# Controler_2_25.net
KiCad netlist of a schematic drawn in EAGLE
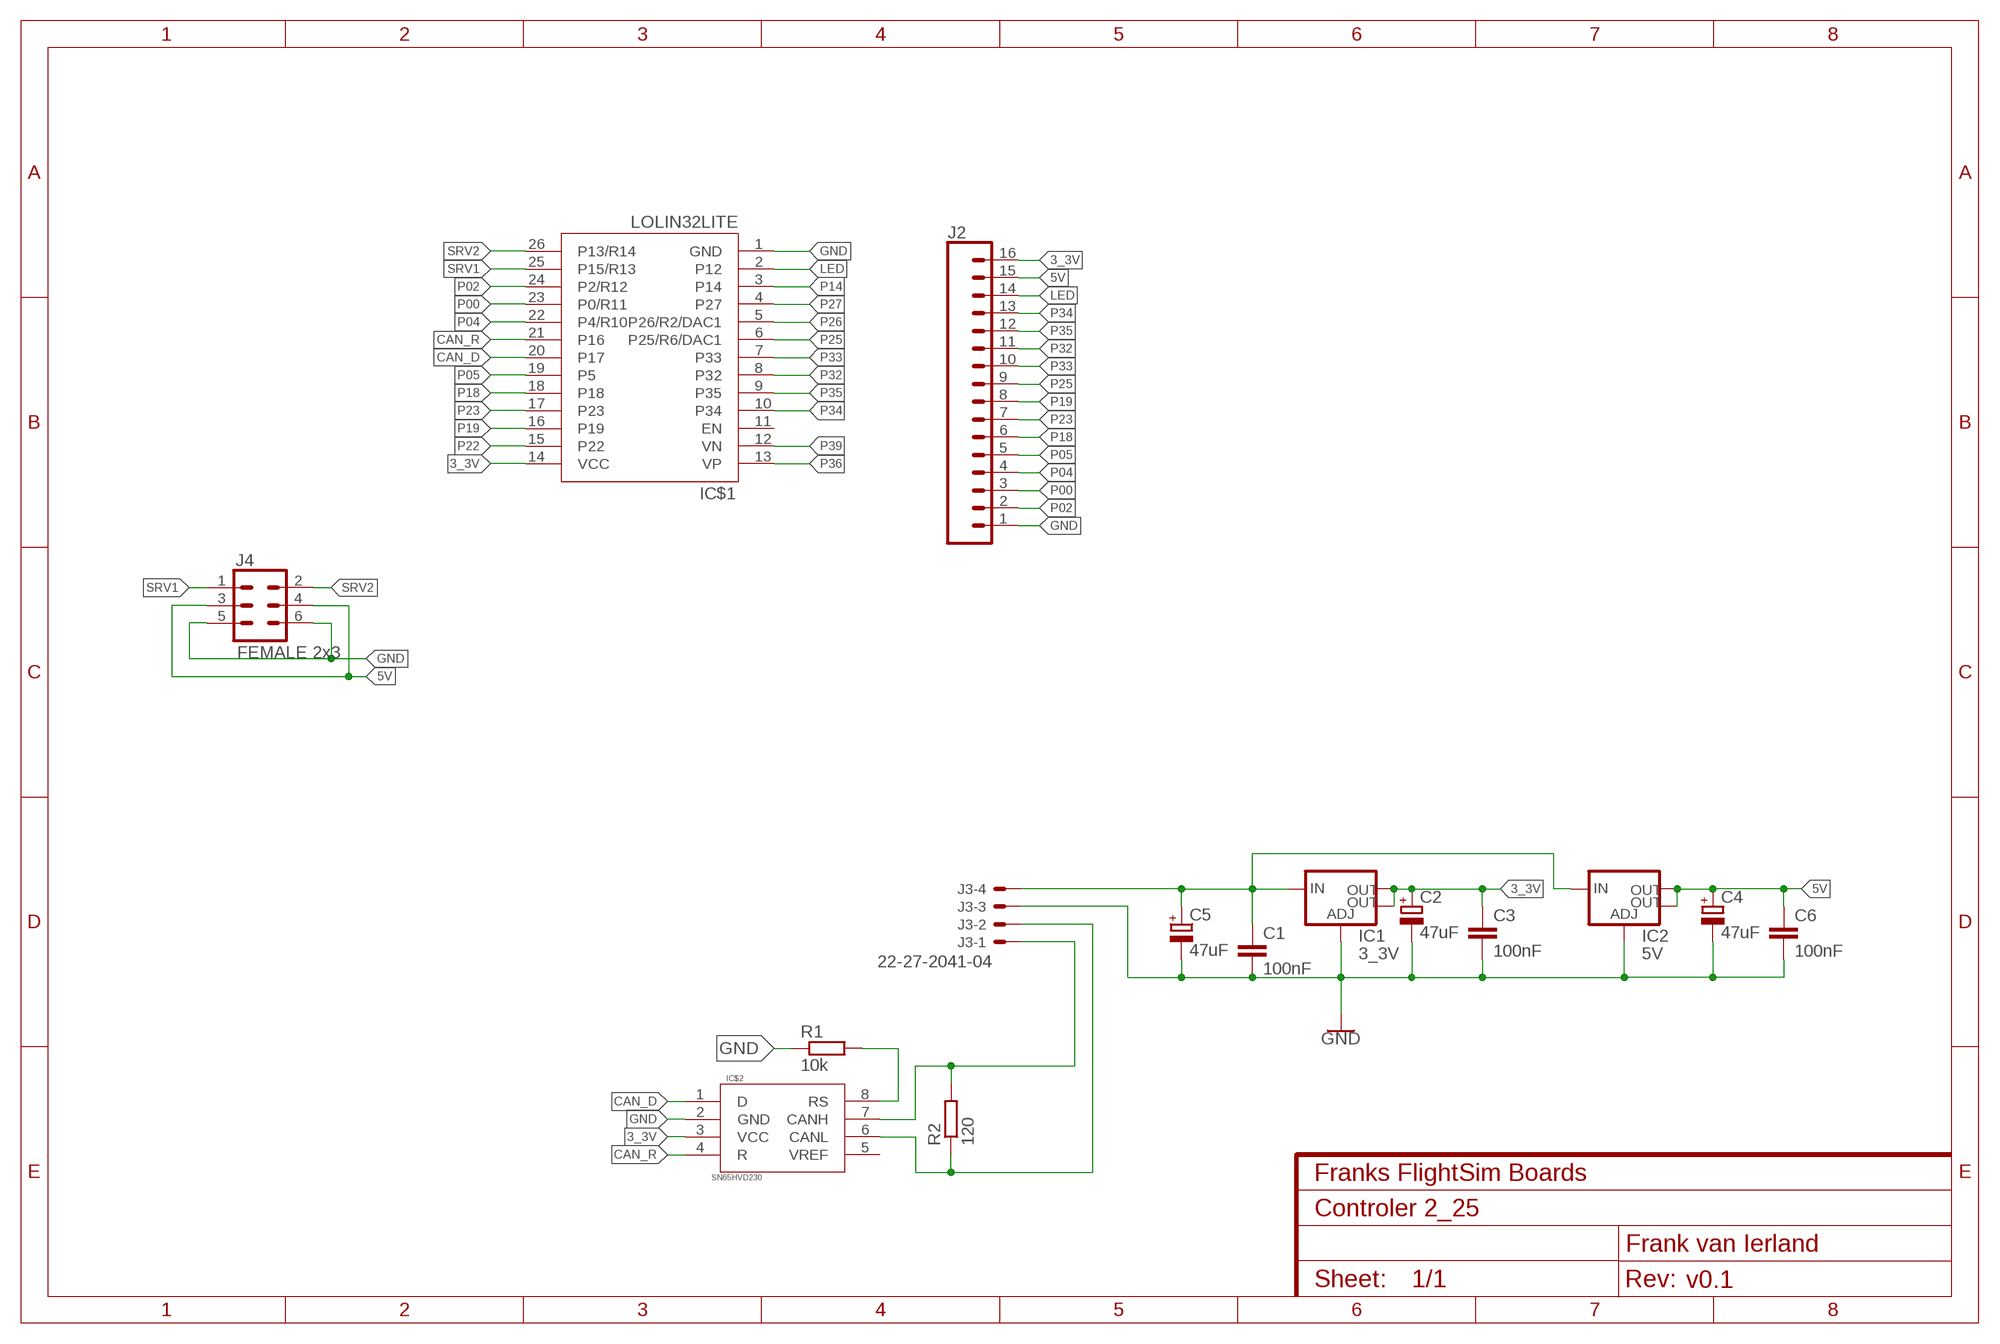
[diagram p0: schematic, sheet 1]

(export (version "E")
  (design (tool "Eeschema 10.0.6"))
  (components
    (comp (ref "C1")
      (value "100nF")
      (footprint "eagle-import:C1206")
      (libsource (lib "eagle-import") (part "C-EUC1206"))
    )
    (comp (ref "C2")
      (value "47uF")
      (footprint "eagle-import:CT3528")
      (libsource (lib "eagle-import") (part "CPOL-EUCT3528"))
    )
    (comp (ref "C3")
      (value "100nF")
      (footprint "eagle-import:C1206")
      (libsource (lib "eagle-import") (part "C-EUC1206"))
    )
    (comp (ref "C4")
      (value "47uF")
      (footprint "eagle-import:CT3528")
      (libsource (lib "eagle-import") (part "CPOL-EUCT3528"))
    )
    (comp (ref "C5")
      (value "47uF")
      (footprint "eagle-import:153CLV-0605")
      (libsource (lib "eagle-import") (part "CPOL-EU153CLV-0605"))
    )
    (comp (ref "C6")
      (value "100nF")
      (footprint "eagle-import:C1206")
      (libsource (lib "eagle-import") (part "C-EUC1206"))
    )
    (comp (ref "IC$1")
      (value "LOLIN32LITE")
      (footprint "eagle-import:LOLIN32LITE")
      (libsource (lib "eagle-import") (part "LOLIN32LITE"))
    )
    (comp (ref "IC$2")
      (value "SN65HVD230")
      (footprint "eagle-import:SO08")
      (libsource (lib "eagle-import") (part "SN65HVD230"))
    )
    (comp (ref "IC1")
      (value "3_3V")
      (footprint "eagle-import:SOT223")
      (libsource (lib "eagle-import") (part "V_REG_LM1117SOT223"))
    )
    (comp (ref "IC2")
      (value "5V")
      (footprint "eagle-import:SOT223")
      (libsource (lib "eagle-import") (part "V_REG_LM1117SOT223"))
    )
    (comp (ref "J2")
      (value "CONN_16")
      (footprint "eagle-import:1X16")
      (libsource (lib "eagle-import") (part "CONN_16"))
    )
    (comp (ref "J3")
      (value "22-27-2041-04")
      (footprint "eagle-import:6410-04")
      (fields (field (name "MF") "MOLEX"))
      (libsource (lib "eagle-import") (part "22-?-0427-2041"))
    )
    (comp (ref "J4")
      (value "FEMALE 2x3")
      (footprint "eagle-import:2X3")
      (libsource (lib "eagle-import") (part "CONN_03X2FEMALE"))
    )
    (comp (ref "R1")
      (value "10k")
      (footprint "eagle-import:M1206")
      (libsource (lib "eagle-import") (part "R-EU_M1206"))
    )
    (comp (ref "R2")
      (value "120")
      (footprint "eagle-import:R1210")
      (libsource (lib "eagle-import") (part "R-EU_R1210"))
    )
  )
  (nets
    (net (code "1") (name "3_3V") (class "Default")
      (node (ref "C2") (pin "-") (pinfunction "+_-") (pintype "passive"))
      (node (ref "C3") (pin "1") (pinfunction "1_1") (pintype "passive"))
      (node (ref "IC$1") (pin "14") (pinfunction "VCC_14") (pintype "power_in"))
      (node (ref "IC$2") (pin "3") (pinfunction "VCC_3") (pintype "bidirectional"))
      (node (ref "IC1") (pin "2") (pinfunction "OUT_2") (pintype "output"))
      (node (ref "IC1") (pin "4") (pinfunction "OUT_4") (pintype "output"))
      (node (ref "J2") (pin "16") (pinfunction "16_16") (pintype "passive"))
    )
    (net (code "2") (name "5V") (class "Default")
      (node (ref "C4") (pin "-") (pinfunction "+_-") (pintype "passive"))
      (node (ref "C6") (pin "1") (pinfunction "1_1") (pintype "passive"))
      (node (ref "IC2") (pin "2") (pinfunction "OUT_2") (pintype "output"))
      (node (ref "IC2") (pin "4") (pinfunction "OUT_4") (pintype "output"))
      (node (ref "J2") (pin "15") (pinfunction "15_15") (pintype "passive"))
      (node (ref "J4") (pin "3") (pinfunction "3_3") (pintype "bidirectional"))
      (node (ref "J4") (pin "4") (pinfunction "4_4") (pintype "bidirectional"))
    )
    (net (code "3") (name "CAN_D") (class "Default")
      (node (ref "IC$1") (pin "20") (pinfunction "P17_20") (pintype "bidirectional"))
      (node (ref "IC$2") (pin "1") (pinfunction "D_1") (pintype "bidirectional"))
    )
    (net (code "4") (name "CAN_R") (class "Default")
      (node (ref "IC$1") (pin "21") (pinfunction "P16_21") (pintype "bidirectional"))
      (node (ref "IC$2") (pin "4") (pinfunction "R_4") (pintype "bidirectional"))
    )
    (net (code "5") (name "GND") (class "Default")
      (node (ref "C1") (pin "2") (pinfunction "2_2") (pintype "passive"))
      (node (ref "C2") (pin "+") (pinfunction "-_+") (pintype "passive"))
      (node (ref "C3") (pin "2") (pinfunction "2_2") (pintype "passive"))
      (node (ref "C4") (pin "+") (pinfunction "-_+") (pintype "passive"))
      (node (ref "C5") (pin "-") (pinfunction "-_-") (pintype "passive"))
      (node (ref "C6") (pin "2") (pinfunction "2_2") (pintype "passive"))
      (node (ref "IC$1") (pin "1") (pinfunction "GND_1") (pintype "power_in"))
      (node (ref "IC$2") (pin "2") (pinfunction "GND_2") (pintype "bidirectional"))
      (node (ref "IC1") (pin "1") (pinfunction "ADJ_1") (pintype "input"))
      (node (ref "IC2") (pin "1") (pinfunction "ADJ_1") (pintype "input"))
      (node (ref "J2") (pin "1") (pinfunction "1_1") (pintype "passive"))
      (node (ref "J3") (pin "3") (pinfunction "S_3") (pintype "passive"))
      (node (ref "J4") (pin "5") (pinfunction "5_5") (pintype "bidirectional"))
      (node (ref "J4") (pin "6") (pinfunction "6_6") (pintype "bidirectional"))
      (node (ref "R1") (pin "1") (pinfunction "1_1") (pintype "passive"))
    )
    (net (code "6") (name "LED") (class "Default")
      (node (ref "IC$1") (pin "2") (pinfunction "P12_2") (pintype "bidirectional"))
      (node (ref "J2") (pin "14") (pinfunction "14_14") (pintype "passive"))
    )
    (net (code "7") (name "Net-(IC$2-CANH)") (class "Default")
      (node (ref "IC$2") (pin "7") (pinfunction "CANH_7") (pintype "bidirectional"))
      (node (ref "J3") (pin "1") (pinfunction "S_1") (pintype "passive"))
      (node (ref "R2") (pin "2") (pinfunction "2_2") (pintype "passive"))
    )
    (net (code "8") (name "Net-(IC$2-CANL)") (class "Default")
      (node (ref "IC$2") (pin "6") (pinfunction "CANL_6") (pintype "bidirectional"))
      (node (ref "J3") (pin "2") (pinfunction "S_2") (pintype "passive"))
      (node (ref "R2") (pin "1") (pinfunction "1_1") (pintype "passive"))
    )
    (net (code "9") (name "Net-(IC$2-RS)") (class "Default")
      (node (ref "IC$2") (pin "8") (pinfunction "RS_8") (pintype "bidirectional"))
      (node (ref "R1") (pin "2") (pinfunction "2_2") (pintype "passive"))
    )
    (net (code "10") (name "Net-(IC1-IN)") (class "Default")
      (node (ref "C1") (pin "1") (pinfunction "1_1") (pintype "passive"))
      (node (ref "C5") (pin "+") (pinfunction "+_+") (pintype "passive"))
      (node (ref "IC1") (pin "3") (pinfunction "IN_3") (pintype "input"))
      (node (ref "IC2") (pin "3") (pinfunction "IN_3") (pintype "input"))
      (node (ref "J3") (pin "4") (pinfunction "S_4") (pintype "passive"))
    )
    (net (code "11") (name "P00") (class "Default")
      (node (ref "IC$1") (pin "23") (pinfunction "P0/R11_23") (pintype "bidirectional"))
      (node (ref "J2") (pin "3") (pinfunction "3_3") (pintype "passive"))
    )
    (net (code "12") (name "P02") (class "Default")
      (node (ref "IC$1") (pin "24") (pinfunction "P2/R12_24") (pintype "bidirectional"))
      (node (ref "J2") (pin "2") (pinfunction "2_2") (pintype "passive"))
    )
    (net (code "13") (name "P04") (class "Default")
      (node (ref "IC$1") (pin "22") (pinfunction "P4/R10_22") (pintype "bidirectional"))
      (node (ref "J2") (pin "4") (pinfunction "4_4") (pintype "passive"))
    )
    (net (code "14") (name "P05") (class "Default")
      (node (ref "IC$1") (pin "19") (pinfunction "P5_19") (pintype "bidirectional"))
      (node (ref "J2") (pin "5") (pinfunction "5_5") (pintype "passive"))
    )
    (net (code "15") (name "P14") (class "Default")
      (node (ref "IC$1") (pin "3") (pinfunction "P14_3") (pintype "bidirectional"))
    )
    (net (code "16") (name "P18") (class "Default")
      (node (ref "IC$1") (pin "18") (pinfunction "P18_18") (pintype "bidirectional"))
      (node (ref "J2") (pin "6") (pinfunction "6_6") (pintype "passive"))
    )
    (net (code "17") (name "P19") (class "Default")
      (node (ref "IC$1") (pin "16") (pinfunction "P19_16") (pintype "bidirectional"))
      (node (ref "J2") (pin "8") (pinfunction "8_8") (pintype "passive"))
    )
    (net (code "18") (name "P22") (class "Default")
      (node (ref "IC$1") (pin "15") (pinfunction "P22_15") (pintype "bidirectional"))
    )
    (net (code "19") (name "P23") (class "Default")
      (node (ref "IC$1") (pin "17") (pinfunction "P23_17") (pintype "bidirectional"))
      (node (ref "J2") (pin "7") (pinfunction "7_7") (pintype "passive"))
    )
    (net (code "20") (name "P25") (class "Default")
      (node (ref "IC$1") (pin "6") (pinfunction "P25/R6/DAC1_6") (pintype "bidirectional"))
      (node (ref "J2") (pin "9") (pinfunction "9_9") (pintype "passive"))
    )
    (net (code "21") (name "P26") (class "Default")
      (node (ref "IC$1") (pin "5") (pinfunction "P26/R2/DAC1_5") (pintype "bidirectional"))
    )
    (net (code "22") (name "P27") (class "Default")
      (node (ref "IC$1") (pin "4") (pinfunction "P27_4") (pintype "bidirectional"))
    )
    (net (code "23") (name "P32") (class "Default")
      (node (ref "IC$1") (pin "8") (pinfunction "P32_8") (pintype "bidirectional"))
      (node (ref "J2") (pin "11") (pinfunction "11_11") (pintype "passive"))
    )
    (net (code "24") (name "P33") (class "Default")
      (node (ref "IC$1") (pin "7") (pinfunction "P33_7") (pintype "bidirectional"))
      (node (ref "J2") (pin "10") (pinfunction "10_10") (pintype "passive"))
    )
    (net (code "25") (name "P34") (class "Default")
      (node (ref "IC$1") (pin "10") (pinfunction "P34_10") (pintype "bidirectional"))
      (node (ref "J2") (pin "13") (pinfunction "13_13") (pintype "passive"))
    )
    (net (code "26") (name "P35") (class "Default")
      (node (ref "IC$1") (pin "9") (pinfunction "P35_9") (pintype "bidirectional"))
      (node (ref "J2") (pin "12") (pinfunction "12_12") (pintype "passive"))
    )
    (net (code "27") (name "P36") (class "Default")
      (node (ref "IC$1") (pin "13") (pinfunction "VP_13") (pintype "bidirectional"))
    )
    (net (code "28") (name "P39") (class "Default")
      (node (ref "IC$1") (pin "12") (pinfunction "VN_12") (pintype "bidirectional"))
    )
    (net (code "29") (name "SRV1") (class "Default")
      (node (ref "IC$1") (pin "25") (pinfunction "P15/R13_25") (pintype "bidirectional"))
      (node (ref "J4") (pin "1") (pinfunction "1_1") (pintype "bidirectional"))
    )
    (net (code "30") (name "SRV2") (class "Default")
      (node (ref "IC$1") (pin "26") (pinfunction "P13/R14_26") (pintype "bidirectional"))
      (node (ref "J4") (pin "2") (pinfunction "2_2") (pintype "bidirectional"))
    )
    (net (code "31") (name "unconnected-(IC$1-EN-Pad11)") (class "Default")
      (node (ref "IC$1") (pin "11") (pinfunction "EN_11") (pintype "bidirectional"))
    )
    (net (code "32") (name "unconnected-(IC$2-VREF-Pad5)") (class "Default")
      (node (ref "IC$2") (pin "5") (pinfunction "VREF_5") (pintype "bidirectional"))
    )
  )
)
